# LPC2148_Engine_Room_ADUM.net
KiCad netlist of a schematic drawn in EAGLE
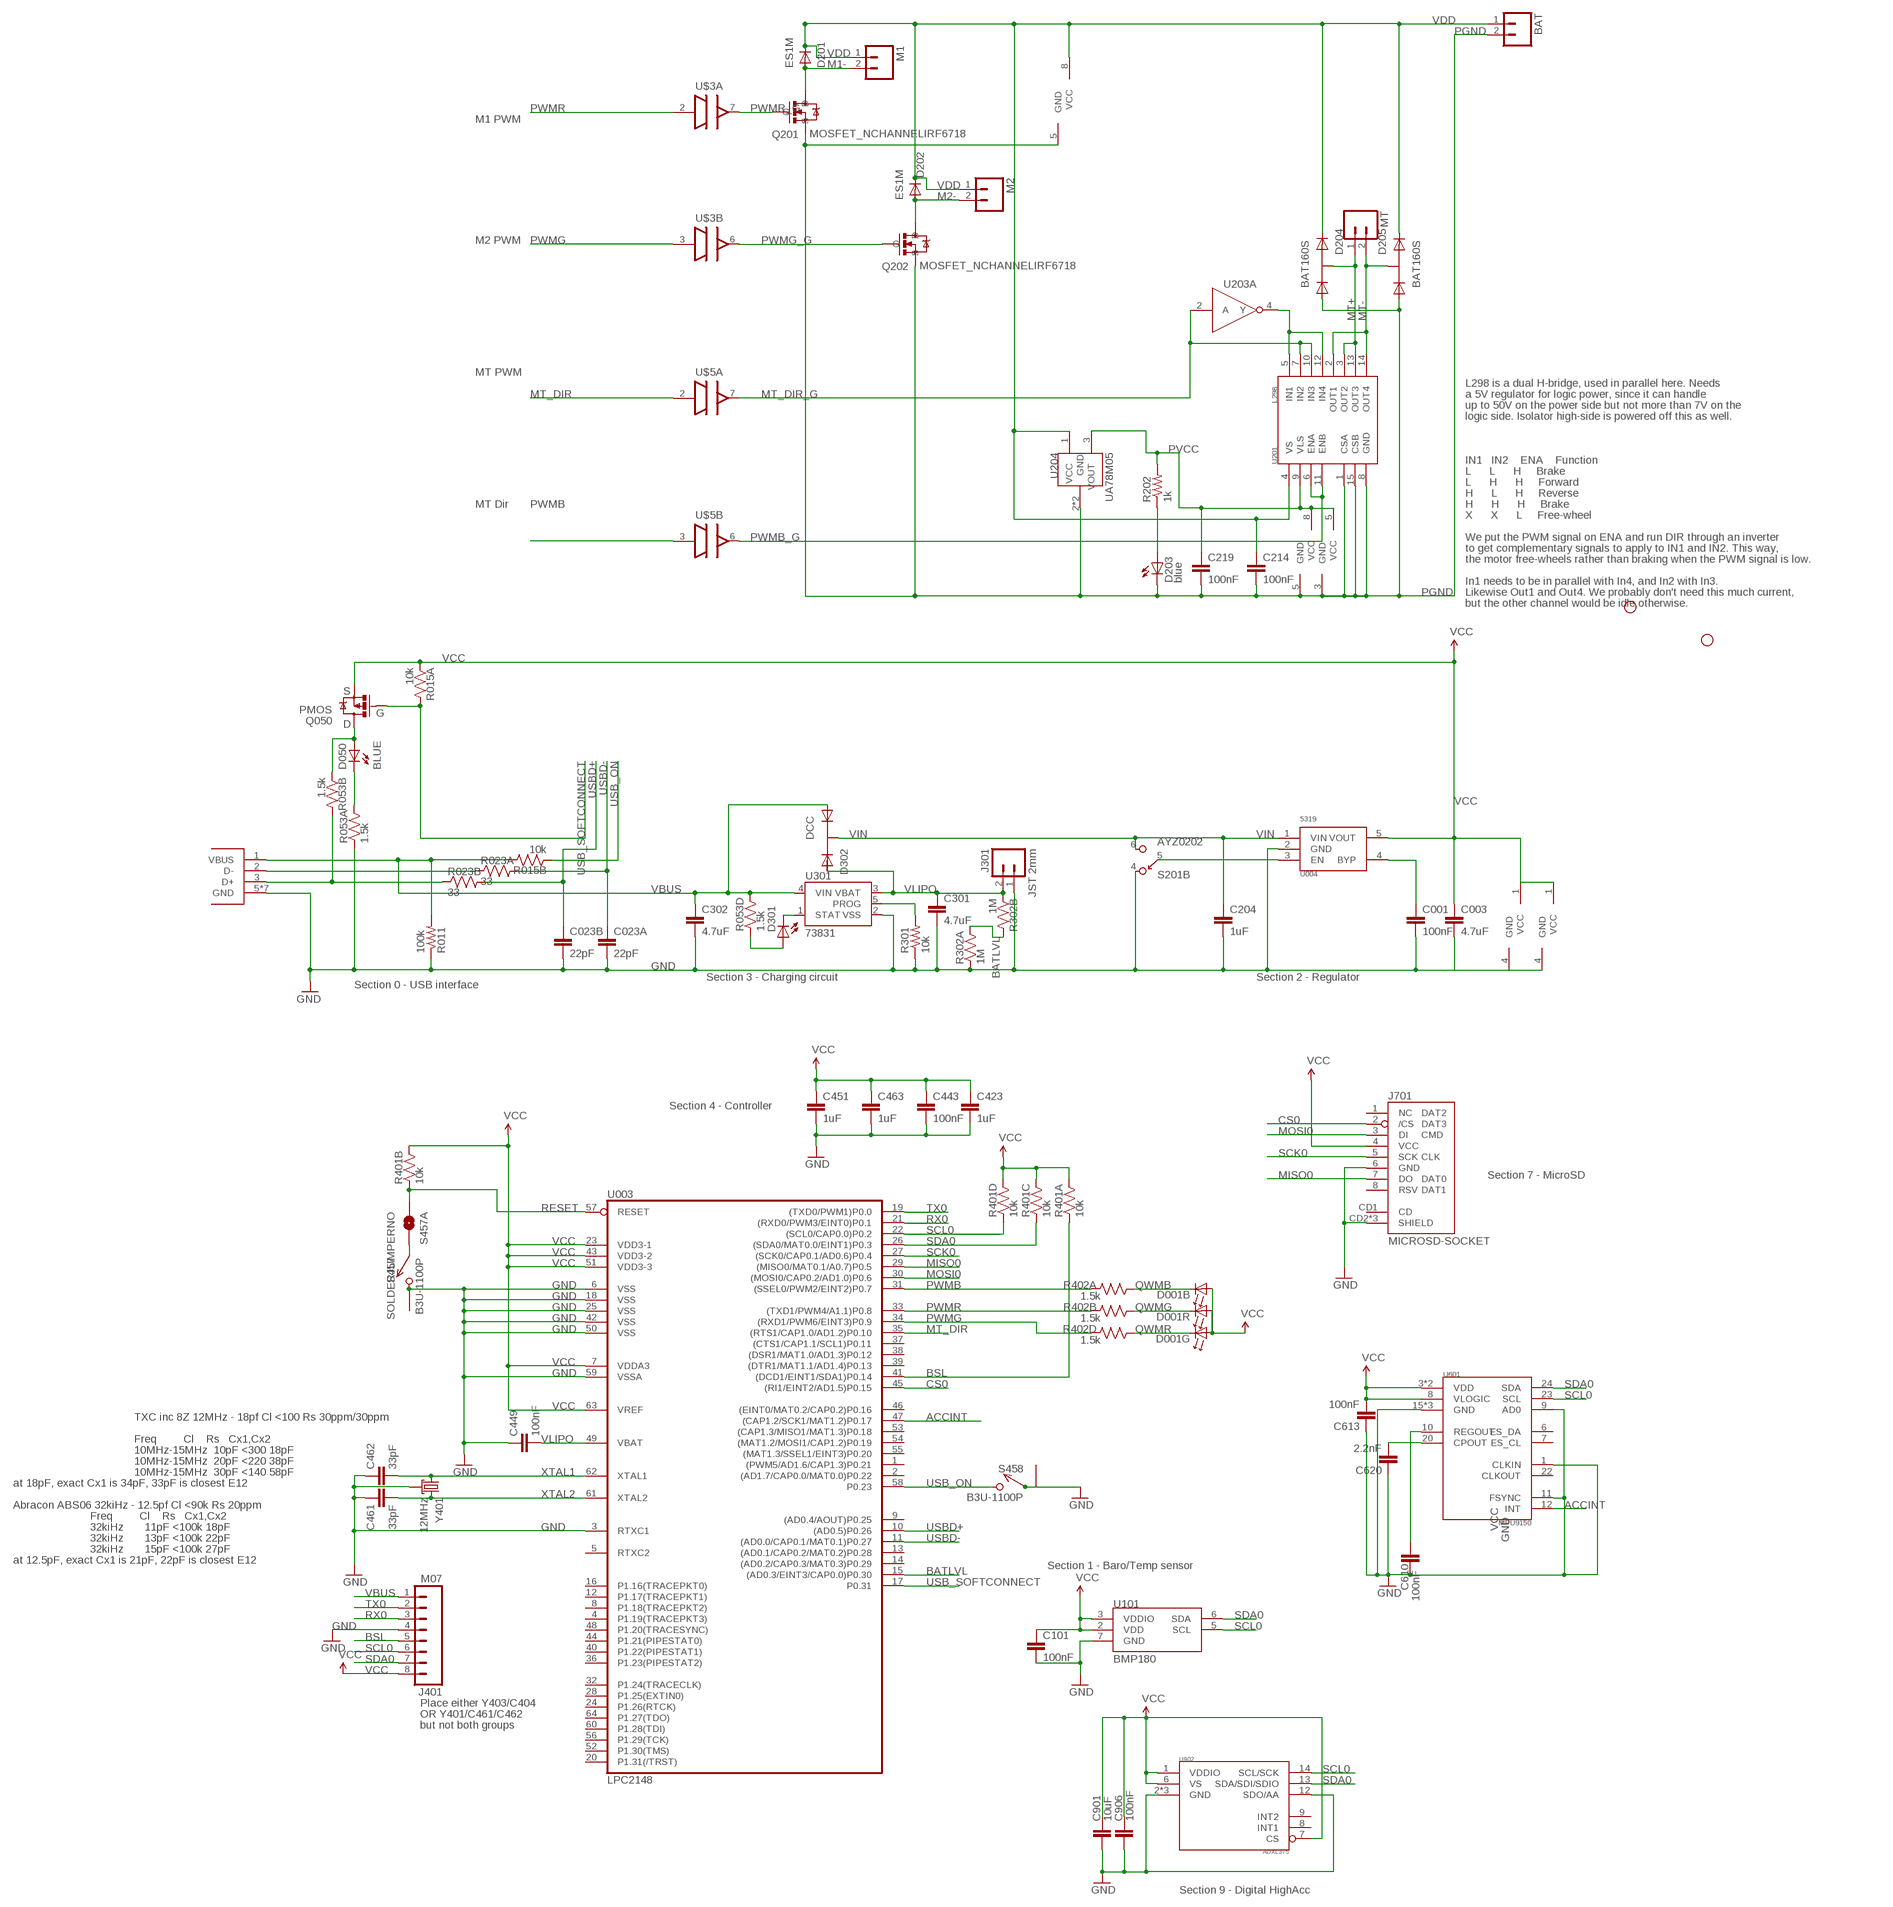
[diagram p0: schematic, sheet 1]

(export (version "E")
  (design (tool "Eeschema 10.0.6"))
  (components
    (comp (ref "BAT")
      (value "M02PTH4")
      (footprint "eagle-import:1X02_XTRA_BIG")
      (libsource (lib "eagle-import") (part "M02PTH4"))
    )
    (comp (ref "C001")
      (value "100nF")
      (footprint "eagle-import:0402-CAP")
      (libsource (lib "eagle-import") (part "CAP0402-CAP"))
    )
    (comp (ref "C003")
      (value "4.7uF")
      (footprint "eagle-import:0402-CAP")
      (libsource (lib "eagle-import") (part "CAP0402-CAP"))
    )
    (comp (ref "C023")
      (value "22pF")
      (footprint "eagle-import:CKCM25")
      (fields (field (name "DIGIKEY") "445-1860-1-ND"))
      (libsource (lib "eagle-import") (part "CKCM25"))
    )
    (comp (ref "C101")
      (value "100nF")
      (footprint "eagle-import:0402-CAP")
      (libsource (lib "eagle-import") (part "CAP0402-CAP"))
    )
    (comp (ref "C204")
      (value "1uF")
      (footprint "eagle-import:0402-CAP")
      (libsource (lib "eagle-import") (part "CAP0402-CAP"))
    )
    (comp (ref "C214")
      (value "100nF")
      (footprint "eagle-import:0402-CAP")
      (libsource (lib "eagle-import") (part "CAP0402-CAP"))
    )
    (comp (ref "C219")
      (value "100nF")
      (footprint "eagle-import:0402-CAP")
      (libsource (lib "eagle-import") (part "CAP0402-CAP"))
    )
    (comp (ref "C301")
      (value "4.7uF")
      (footprint "eagle-import:0402-CAP")
      (libsource (lib "eagle-import") (part "CAP0402-CAP"))
    )
    (comp (ref "C302")
      (value "4.7uF")
      (footprint "eagle-import:0402-CAP")
      (libsource (lib "eagle-import") (part "CAP0402-CAP"))
    )
    (comp (ref "C423")
      (value "1uF")
      (footprint "eagle-import:0402-CAP")
      (libsource (lib "eagle-import") (part "CAP0402-CAP"))
    )
    (comp (ref "C443")
      (value "100nF")
      (footprint "eagle-import:0402-CAP")
      (libsource (lib "eagle-import") (part "CAP0402-CAP"))
    )
    (comp (ref "C449")
      (value "100nF")
      (footprint "eagle-import:0402-CAP")
      (libsource (lib "eagle-import") (part "CAP0402-CAP"))
    )
    (comp (ref "C451")
      (value "1uF")
      (footprint "eagle-import:0402-CAP")
      (libsource (lib "eagle-import") (part "CAP0402-CAP"))
    )
    (comp (ref "C461")
      (value "33pF")
      (footprint "eagle-import:0402-CAP")
      (libsource (lib "eagle-import") (part "CAP0402-CAP"))
    )
    (comp (ref "C462")
      (value "33pF")
      (footprint "eagle-import:0402-CAP")
      (libsource (lib "eagle-import") (part "CAP0402-CAP"))
    )
    (comp (ref "C463")
      (value "1uF")
      (footprint "eagle-import:0402-CAP")
      (libsource (lib "eagle-import") (part "CAP0402-CAP"))
    )
    (comp (ref "C610")
      (value "100nF")
      (footprint "eagle-import:0402-CAP")
      (libsource (lib "eagle-import") (part "CAP0402-CAP"))
    )
    (comp (ref "C613")
      (value "100nF")
      (footprint "eagle-import:0402-CAP")
      (libsource (lib "eagle-import") (part "CAP0402-CAP"))
    )
    (comp (ref "C620")
      (value "2.2nF")
      (footprint "eagle-import:0402-CAP")
      (libsource (lib "eagle-import") (part "CAP0402-CAP"))
    )
    (comp (ref "C901")
      (value "10uF")
      (footprint "eagle-import:0603-CAP")
      (libsource (lib "eagle-import") (part "CAP0603-CAP"))
    )
    (comp (ref "C906")
      (value "100nF")
      (footprint "eagle-import:0402-CAP")
      (libsource (lib "eagle-import") (part "SparkFun-Passives_CAP0402-CAP"))
    )
    (comp (ref "D001")
      (value "SMLP36RGB2W(R)")
      (footprint "eagle-import:SMLP36")
      (fields (field (name "DIGIKEY") "846-1097-1-ND"))
      (libsource (lib "eagle-import") (part "SMLP36RGB2W(R)"))
    )
    (comp (ref "D050")
      (value "BLUE")
      (footprint "eagle-import:LED-0603")
      (libsource (lib "eagle-import") (part "LED0603"))
    )
    (comp (ref "D201")
      (value "ES1M")
      (footprint "eagle-import:DO-214AC")
      (libsource (lib "eagle-import") (part "DIODE-DO-214AC"))
    )
    (comp (ref "D202")
      (value "ES1M")
      (footprint "eagle-import:DO-214AC")
      (libsource (lib "eagle-import") (part "DIODE-DO-214AC"))
    )
    (comp (ref "D203")
      (value "blue")
      (footprint "eagle-import:LED-0603")
      (libsource (lib "eagle-import") (part "LED0603"))
    )
    (comp (ref "D204")
      (value "BAT160S")
      (footprint "eagle-import:SOT-223")
      (libsource (lib "eagle-import") (part "BAT160S"))
    )
    (comp (ref "D205")
      (value "BAT160S")
      (footprint "eagle-import:SOT-223")
      (libsource (lib "eagle-import") (part "BAT160S"))
    )
    (comp (ref "D301")
      (value "YELLOW")
      (footprint "eagle-import:LED-0603")
      (libsource (lib "eagle-import") (part "LED0603"))
    )
    (comp (ref "D302")
      (value "DCC")
      (footprint "eagle-import:SOT-23-3")
      (libsource (lib "eagle-import") (part "PMEG2005CT"))
    )
    (comp (ref "J004")
      (value "USB_MICROB_JSTGCT")
      (footprint "eagle-import:USB_MICROB_3075")
      (libsource (lib "eagle-import") (part "USB_MICROB_JSTGCT"))
    )
    (comp (ref "J301")
      (value "JST 2mm")
      (footprint "eagle-import:JST-2-SMD")
      (libsource (lib "eagle-import") (part "M02-JST-2MM-SMT"))
    )
    (comp (ref "J401")
      (value "M07")
      (footprint "eagle-import:1X08")
      (libsource (lib "eagle-import") (part "M081X08"))
    )
    (comp (ref "J701")
      (value "MICROSD-SOCKET")
      (footprint "eagle-import:MICROSD-SOCKET-PP")
      (libsource (lib "eagle-import") (part "MICROSD-SOCKET"))
    )
    (comp (ref "JP1")
      (value "STAND-OFF")
      (footprint "eagle-import:STAND-OFF")
      (libsource (lib "eagle-import") (part "STAND-OFF"))
    )
    (comp (ref "JP2")
      (value "STAND-OFF")
      (footprint "eagle-import:STAND-OFF")
      (libsource (lib "eagle-import") (part "STAND-OFF"))
    )
    (comp (ref "M1")
      (value "M02PTH4")
      (footprint "eagle-import:1X02_XTRA_BIG")
      (libsource (lib "eagle-import") (part "M02PTH4"))
    )
    (comp (ref "M2")
      (value "M02PTH4")
      (footprint "eagle-import:1X02_XTRA_BIG")
      (libsource (lib "eagle-import") (part "M02PTH4"))
    )
    (comp (ref "MT")
      (value "M02PTH")
      (footprint "eagle-import:1X02")
      (libsource (lib "eagle-import") (part "M02PTH"))
    )
    (comp (ref "Q050")
      (value "PMOS")
      (footprint "eagle-import:SOT23-3")
      (libsource (lib "eagle-import") (part "MOSFET-PCHANNELSMD"))
    )
    (comp (ref "Q201")
      (value "MOSFET_NCHANNELIRF6718")
      (footprint "eagle-import:DIRECTFET_L6")
      (libsource (lib "eagle-import") (part "MOSFET_NCHANNELIRF6718"))
    )
    (comp (ref "Q202")
      (value "MOSFET_NCHANNELIRF6718")
      (footprint "eagle-import:DIRECTFET_L6")
      (libsource (lib "eagle-import") (part "MOSFET_NCHANNELIRF6718"))
    )
    (comp (ref "R011")
      (value "100k")
      (footprint "eagle-import:0402-RES")
      (libsource (lib "eagle-import") (part "RESISTOR0402-RES"))
    )
    (comp (ref "R015")
      (value "10k")
      (footprint "eagle-import:CRA02")
      (fields (field (name "DIGIKEY") "Y5103CT-ND"))
      (libsource (lib "eagle-import") (part "RP2EXB24V"))
    )
    (comp (ref "R023")
      (value "33")
      (footprint "eagle-import:CRA02")
      (libsource (lib "eagle-import") (part "RP2EXB24V"))
    )
    (comp (ref "R053")
      (value "1.5k")
      (footprint "eagle-import:CRA04")
      (fields (field (name "DIGIKEY") "CRA4S81.5KCT-ND"))
      (libsource (lib "eagle-import") (part "RP404"))
    )
    (comp (ref "R202")
      (value "1k")
      (footprint "eagle-import:0402-RES")
      (libsource (lib "eagle-import") (part "RESISTOR0402-RES"))
    )
    (comp (ref "R301")
      (value "10k")
      (footprint "eagle-import:0402-RES")
      (libsource (lib "eagle-import") (part "RESISTOR0402-RES"))
    )
    (comp (ref "R302")
      (value "1M")
      (footprint "eagle-import:CRA02")
      (libsource (lib "eagle-import") (part "RP2EXB24V"))
    )
    (comp (ref "R401")
      (value "10k")
      (footprint "eagle-import:CRA04")
      (fields (field (name "DIGIKEY") "CRA4S810KCT-ND"))
      (libsource (lib "eagle-import") (part "RP404"))
    )
    (comp (ref "R402")
      (value "1.5k")
      (footprint "eagle-import:CRA04")
      (fields (field (name "DIGIKEY") "CRA4S81.5KCT-ND"))
      (libsource (lib "eagle-import") (part "RP404"))
    )
    (comp (ref "S201")
      (value "AYZ0202")
      (footprint "eagle-import:AYZ0202")
      (libsource (lib "eagle-import") (part "AYZ0202"))
    )
    (comp (ref "S457")
      (value "B3U-1100P")
      (footprint "eagle-import:B3U-1100P")
      (fields (field (name "DIGIKEY") "SW1021CT-ND"))
      (libsource (lib "eagle-import") (part "B3U-1100P"))
    )
    (comp (ref "S457A")
      (value "SOLDERJUMPERNO")
      (footprint "eagle-import:SJ_2S-NO")
      (libsource (lib "eagle-import") (part "SOLDERJUMPERNO"))
    )
    (comp (ref "S458")
      (value "B3U-1100P")
      (footprint "eagle-import:B3U-1100P")
      (fields (field (name "DIGIKEY") "SW1021CT-ND"))
      (libsource (lib "eagle-import") (part "B3U-1100P"))
    )
    (comp (ref "U$3")
      (value "ADUM3221")
      (footprint "eagle-import:SO8N")
      (libsource (lib "eagle-import") (part "ADUM3221"))
    )
    (comp (ref "U$5")
      (value "ADUM3221")
      (footprint "eagle-import:SO8N")
      (libsource (lib "eagle-import") (part "ADUM3221"))
    )
    (comp (ref "U003")
      (value "LPC2148")
      (footprint "eagle-import:SQFP-S-10X10-64")
      (libsource (lib "eagle-import") (part "LPC213X"))
    )
    (comp (ref "U004")
      (value "5319")
      (footprint "eagle-import:SOT-23-5")
      (libsource (lib "eagle-import") (part "MIC5319D5"))
    )
    (comp (ref "U101")
      (value "BMP180")
      (footprint "eagle-import:BMP180")
      (libsource (lib "eagle-import") (part "BMP180"))
    )
    (comp (ref "U201")
      (value "L298")
      (footprint "eagle-import:MULTIWATT15")
      (libsource (lib "eagle-import") (part "L298"))
    )
    (comp (ref "U203")
      (value "MC74VHC1G04")
      (footprint "eagle-import:SOT-23-5")
      (libsource (lib "eagle-import") (part "MC74VHC1G04"))
    )
    (comp (ref "U204")
      (value "UA78M05")
      (footprint "eagle-import:SOT-223")
      (libsource (lib "eagle-import") (part "UA78M05"))
    )
    (comp (ref "U301")
      (value "73831")
      (footprint "eagle-import:SOT23-5")
      (libsource (lib "eagle-import") (part "MCP73831"))
    )
    (comp (ref "U601")
      (value "MPU9150")
      (footprint "eagle-import:LLGA24")
      (libsource (lib "eagle-import") (part "MPU9150"))
    )
    (comp (ref "U902")
      (value "ADXL375")
      (footprint "eagle-import:ADXL375")
      (libsource (lib "eagle-import") (part "ADXL375"))
    )
    (comp (ref "Y401")
      (value "12MHz")
      (footprint "eagle-import:CRYSTAL_SMD_2MM_2_5MM")
      (libsource (lib "eagle-import") (part "CX2520"))
    )
  )
  (nets
    (net (code "1") (name "/ACCINT") (class "Default")
      (node (ref "U003") (pin "47") (pinfunction "(CAP1.2/SCK1/MAT1.2)P0.17_47") (pintype "bidirectional"))
      (node (ref "U601") (pin "12") (pinfunction "INT_12") (pintype "bidirectional"))
    )
    (net (code "2") (name "/BATLVL") (class "Default")
      (node (ref "R302") (pin "3") (pinfunction "2_3") (pintype "passive"))
      (node (ref "R302") (pin "4") (pinfunction "2_4") (pintype "passive"))
      (node (ref "U003") (pin "15") (pinfunction "(AD0.3/EINT3/CAP0.0)P0.30_15") (pintype "bidirectional"))
    )
    (net (code "3") (name "/BSL") (class "Default")
      (node (ref "J401") (pin "5") (pinfunction "5_5") (pintype "passive"))
      (node (ref "R401") (pin "1") (pinfunction "1_1") (pintype "passive"))
      (node (ref "U003") (pin "41") (pinfunction "(DCD1/EINT1/SDA1)P0.14_41") (pintype "bidirectional"))
    )
    (net (code "4") (name "/CS0") (class "Default")
      (node (ref "J701") (pin "2") (pinfunction "/CS_2") (pintype "bidirectional"))
      (node (ref "U003") (pin "45") (pinfunction "(RI1/EINT2/AD1.5)P0.15_45") (pintype "bidirectional"))
    )
    (net (code "5") (name "/M1-") (class "Default")
      (node (ref "D201") (pin "A") (pinfunction "A_A") (pintype "passive"))
      (node (ref "M1") (pin "2") (pinfunction "2_2") (pintype "passive"))
      (node (ref "Q201") (pin "D1") (pinfunction "D_D1") (pintype "passive"))
      (node (ref "Q201") (pin "D2") (pinfunction "D_D2") (pintype "passive"))
    )
    (net (code "6") (name "/M2-") (class "Default")
      (node (ref "D202") (pin "A") (pinfunction "A_A") (pintype "passive"))
      (node (ref "M2") (pin "2") (pinfunction "2_2") (pintype "passive"))
      (node (ref "Q202") (pin "D1") (pinfunction "D_D1") (pintype "passive"))
      (node (ref "Q202") (pin "D2") (pinfunction "D_D2") (pintype "passive"))
    )
    (net (code "7") (name "/MISO0") (class "Default")
      (node (ref "J701") (pin "7") (pinfunction "DO_7") (pintype "bidirectional"))
      (node (ref "U003") (pin "29") (pinfunction "(MISO0/MAT0.1/A0.7)P0.5_29") (pintype "bidirectional"))
    )
    (net (code "8") (name "/MOSI0") (class "Default")
      (node (ref "J701") (pin "3") (pinfunction "DI_3") (pintype "bidirectional"))
      (node (ref "U003") (pin "30") (pinfunction "(MOSI0/CAP0.2/AD1.0)P0.6_30") (pintype "bidirectional"))
    )
    (net (code "9") (name "/MT+") (class "Default")
      (node (ref "D204") (pin "4") (pinfunction "K1A2_4") (pintype "passive"))
      (node (ref "MT") (pin "1") (pinfunction "1_1") (pintype "passive"))
      (node (ref "U201") (pin "13") (pinfunction "OUT3_13") (pintype "bidirectional"))
      (node (ref "U201") (pin "3") (pinfunction "OUT2_3") (pintype "bidirectional"))
    )
    (net (code "10") (name "/MT-") (class "Default")
      (node (ref "D205") (pin "4") (pinfunction "K1A2_4") (pintype "passive"))
      (node (ref "MT") (pin "2") (pinfunction "2_2") (pintype "passive"))
      (node (ref "U201") (pin "14") (pinfunction "OUT4_14") (pintype "bidirectional"))
      (node (ref "U201") (pin "2") (pinfunction "OUT1_2") (pintype "bidirectional"))
    )
    (net (code "11") (name "/MT_DIR") (class "Default")
      (node (ref "U$5") (pin "2") (pinfunction "IN_2") (pintype "input"))
      (node (ref "U003") (pin "35") (pinfunction "(RTS1/CAP1.0/AD1.2)P0.10_35") (pintype "bidirectional"))
    )
    (net (code "12") (name "/MT_DIR_G") (class "Default")
      (node (ref "U$5") (pin "7") (pinfunction "OUT_7") (pintype "bidirectional"))
      (node (ref "U201") (pin "10") (pinfunction "IN3_10") (pintype "bidirectional"))
      (node (ref "U201") (pin "7") (pinfunction "IN2_7") (pintype "bidirectional"))
      (node (ref "U203") (pin "2") (pinfunction "A_2") (pintype "input"))
    )
    (net (code "13") (name "/PGND") (class "Default")
      (node (ref "BAT") (pin "2") (pinfunction "2_2") (pintype "passive"))
      (node (ref "C214") (pin "2") (pinfunction "2_2") (pintype "passive"))
      (node (ref "C219") (pin "2") (pinfunction "2_2") (pintype "passive"))
      (node (ref "D203") (pin "C") (pinfunction "C_C") (pintype "passive"))
      (node (ref "D204") (pin "1") (pinfunction "A1_1") (pintype "passive"))
      (node (ref "D205") (pin "1") (pinfunction "A1_1") (pintype "passive"))
      (node (ref "Q201") (pin "S") (pinfunction "S_S") (pintype "passive"))
      (node (ref "Q202") (pin "S") (pinfunction "S_S") (pintype "passive"))
      (node (ref "U$3") (pin "5") (pinfunction "GND_5") (pintype "bidirectional"))
      (node (ref "U$5") (pin "5") (pinfunction "GND_5") (pintype "bidirectional"))
      (node (ref "U201") (pin "1") (pinfunction "CSA_1") (pintype "bidirectional"))
      (node (ref "U201") (pin "15") (pinfunction "CSB_15") (pintype "bidirectional"))
      (node (ref "U201") (pin "8") (pinfunction "GND_8") (pintype "bidirectional"))
      (node (ref "U203") (pin "3") (pinfunction "GND_3") (pintype "bidirectional"))
      (node (ref "U204") (pin "2") (pinfunction "GND_2") (pintype "bidirectional"))
      (node (ref "U204") (pin "4") (pinfunction "GND_4") (pintype "bidirectional"))
    )
    (net (code "14") (name "/PVCC") (class "Default")
      (node (ref "C219") (pin "1") (pinfunction "1_1") (pintype "passive"))
      (node (ref "R202") (pin "2") (pinfunction "2_2") (pintype "passive"))
      (node (ref "U$5") (pin "8") (pinfunction "VCC_8") (pintype "bidirectional"))
      (node (ref "U201") (pin "9") (pinfunction "VLS_9") (pintype "bidirectional"))
      (node (ref "U203") (pin "5") (pinfunction "VCC_5") (pintype "bidirectional"))
      (node (ref "U204") (pin "3") (pinfunction "VOUT_3") (pintype "bidirectional"))
    )
    (net (code "15") (name "/PWMB") (class "Default")
      (node (ref "R402") (pin "8") (pinfunction "2_8") (pintype "passive"))
      (node (ref "U$5") (pin "3") (pinfunction "IN_3") (pintype "input"))
      (node (ref "U003") (pin "31") (pinfunction "(SSEL0/PWM2/EINT2)P0.7_31") (pintype "bidirectional"))
    )
    (net (code "16") (name "/PWMB_G") (class "Default")
      (node (ref "U$5") (pin "6") (pinfunction "OUT_6") (pintype "bidirectional"))
      (node (ref "U201") (pin "11") (pinfunction "ENB_11") (pintype "bidirectional"))
      (node (ref "U201") (pin "6") (pinfunction "ENA_6") (pintype "bidirectional"))
    )
    (net (code "17") (name "/PWMG") (class "Default")
      (node (ref "R402") (pin "5") (pinfunction "2_5") (pintype "passive"))
      (node (ref "U$3") (pin "3") (pinfunction "IN_3") (pintype "input"))
      (node (ref "U003") (pin "34") (pinfunction "(RXD1/PWM6/EINT3)P0.9_34") (pintype "bidirectional"))
    )
    (net (code "18") (name "/PWMG_G") (class "Default")
      (node (ref "Q202") (pin "G") (pinfunction "G_G") (pintype "passive"))
      (node (ref "U$3") (pin "6") (pinfunction "OUT_6") (pintype "bidirectional"))
    )
    (net (code "19") (name "/PWMR") (class "Default")
      (node (ref "R402") (pin "7") (pinfunction "2_7") (pintype "passive"))
      (node (ref "U$3") (pin "2") (pinfunction "IN_2") (pintype "input"))
      (node (ref "U003") (pin "33") (pinfunction "(TXD1/PWM4/A1.1)P0.8_33") (pintype "bidirectional"))
    )
    (net (code "20") (name "/PWMR_G") (class "Default")
      (node (ref "Q201") (pin "G") (pinfunction "G_G") (pintype "passive"))
      (node (ref "U$3") (pin "7") (pinfunction "OUT_7") (pintype "bidirectional"))
    )
    (net (code "21") (name "/QWMB") (class "Default")
      (node (ref "D001") (pin "1") (pinfunction "C_1") (pintype "passive"))
      (node (ref "R402") (pin "1") (pinfunction "1_1") (pintype "passive"))
    )
    (net (code "22") (name "/QWMG") (class "Default")
      (node (ref "D001") (pin "5") (pinfunction "C_5") (pintype "passive"))
      (node (ref "R402") (pin "4") (pinfunction "1_4") (pintype "passive"))
    )
    (net (code "23") (name "/QWMR") (class "Default")
      (node (ref "D001") (pin "3") (pinfunction "C_3") (pintype "passive"))
      (node (ref "R402") (pin "2") (pinfunction "1_2") (pintype "passive"))
    )
    (net (code "24") (name "/RESET") (class "Default")
      (node (ref "R401") (pin "2") (pinfunction "1_2") (pintype "passive"))
      (node (ref "S457A") (pin "1") (pinfunction "1_1") (pintype "passive"))
      (node (ref "U003") (pin "57") (pinfunction "RESET_57") (pintype "input"))
    )
    (net (code "25") (name "/RX0") (class "Default")
      (node (ref "J401") (pin "3") (pinfunction "3_3") (pintype "passive"))
      (node (ref "U003") (pin "21") (pinfunction "(RXD0/PWM3/EINT0)P0.1_21") (pintype "bidirectional"))
    )
    (net (code "26") (name "/SCK0") (class "Default")
      (node (ref "J701") (pin "5") (pinfunction "SCK_5") (pintype "bidirectional"))
      (node (ref "U003") (pin "27") (pinfunction "(SCK0/CAP0.1/AD0.6)P0.4_27") (pintype "bidirectional"))
    )
    (net (code "27") (name "/SCL0") (class "Default")
      (node (ref "J401") (pin "6") (pinfunction "6_6") (pintype "passive"))
      (node (ref "R401") (pin "4") (pinfunction "1_4") (pintype "passive"))
      (node (ref "U003") (pin "22") (pinfunction "(SCL0/CAP0.0)P0.2_22") (pintype "bidirectional"))
      (node (ref "U101") (pin "5") (pinfunction "SCL_5") (pintype "input"))
      (node (ref "U601") (pin "23") (pinfunction "SCL_23") (pintype "bidirectional"))
      (node (ref "U902") (pin "14") (pinfunction "SCL/SCK_14") (pintype "input"))
    )
    (net (code "28") (name "/SDA0") (class "Default")
      (node (ref "J401") (pin "7") (pinfunction "7_7") (pintype "passive"))
      (node (ref "R401") (pin "3") (pinfunction "1_3") (pintype "passive"))
      (node (ref "U003") (pin "26") (pinfunction "(SDA0/MAT0.0/EINT1)P0.3_26") (pintype "bidirectional"))
      (node (ref "U101") (pin "6") (pinfunction "SDA_6") (pintype "bidirectional"))
      (node (ref "U601") (pin "24") (pinfunction "SDA_24") (pintype "bidirectional"))
      (node (ref "U902") (pin "13") (pinfunction "SDA/SDI/SDIO_13") (pintype "bidirectional"))
    )
    (net (code "29") (name "/TX0") (class "Default")
      (node (ref "J401") (pin "2") (pinfunction "2_2") (pintype "passive"))
      (node (ref "U003") (pin "19") (pinfunction "(TXD0/PWM1)P0.0_19") (pintype "bidirectional"))
    )
    (net (code "30") (name "/USBD+") (class "Default")
      (node (ref "C023") (pin "2") (pinfunction "1_2") (pintype "passive"))
      (node (ref "R023") (pin "3") (pinfunction "2_3") (pintype "passive"))
      (node (ref "U003") (pin "10") (pinfunction "(AD0.5)P0.26_10") (pintype "bidirectional"))
    )
    (net (code "31") (name "/USBD-") (class "Default")
      (node (ref "C023") (pin "1") (pinfunction "1_1") (pintype "passive"))
      (node (ref "R023") (pin "4") (pinfunction "2_4") (pintype "passive"))
      (node (ref "U003") (pin "11") (pinfunction "(AD0.0/CAP0.1/MAT0.1)P0.27_11") (pintype "bidirectional"))
    )
    (net (code "32") (name "/USB_ON") (class "Default")
      (node (ref "R015") (pin "2") (pinfunction "1_2") (pintype "passive"))
      (node (ref "S458") (pin "P$2") (pinfunction "2_P$2") (pintype "bidirectional"))
      (node (ref "U003") (pin "58") (pinfunction "P0.23_58") (pintype "bidirectional"))
    )
    (net (code "33") (name "/USB_SOFTCONNECT") (class "Default")
      (node (ref "Q050") (pin "1") (pinfunction "G_1") (pintype "passive"))
      (node (ref "R015") (pin "4") (pinfunction "2_4") (pintype "passive"))
      (node (ref "U003") (pin "17") (pinfunction "P0.31_17") (pintype "output"))
    )
    (net (code "34") (name "/VBUS") (class "Default")
      (node (ref "C302") (pin "1") (pinfunction "1_1") (pintype "passive"))
      (node (ref "D302") (pin "1") (pinfunction "A1_1") (pintype "passive"))
      (node (ref "J004") (pin "1") (pinfunction "VBUS_1") (pintype "bidirectional"))
      (node (ref "J401") (pin "1") (pinfunction "1_1") (pintype "passive"))
      (node (ref "R011") (pin "2") (pinfunction "2_2") (pintype "passive"))
      (node (ref "R015") (pin "3") (pinfunction "2_3") (pintype "passive"))
      (node (ref "R053") (pin "5") (pinfunction "2_5") (pintype "passive"))
      (node (ref "U301") (pin "4") (pinfunction "VIN_4") (pintype "power_in"))
    )
    (net (code "35") (name "/VDD") (class "Default")
      (node (ref "BAT") (pin "1") (pinfunction "1_1") (pintype "passive"))
      (node (ref "C214") (pin "1") (pinfunction "1_1") (pintype "passive"))
      (node (ref "D201") (pin "C") (pinfunction "C_C") (pintype "passive"))
      (node (ref "D202") (pin "C") (pinfunction "C_C") (pintype "passive"))
      (node (ref "D204") (pin "3") (pinfunction "K2_3") (pintype "passive"))
      (node (ref "D205") (pin "3") (pinfunction "K2_3") (pintype "passive"))
      (node (ref "M1") (pin "1") (pinfunction "1_1") (pintype "passive"))
      (node (ref "M2") (pin "1") (pinfunction "1_1") (pintype "passive"))
      (node (ref "U$3") (pin "8") (pinfunction "VCC_8") (pintype "bidirectional"))
      (node (ref "U201") (pin "4") (pinfunction "VS_4") (pintype "bidirectional"))
      (node (ref "U204") (pin "1") (pinfunction "VCC_1") (pintype "bidirectional"))
    )
    (net (code "36") (name "/VIN") (class "Default")
      (node (ref "C204") (pin "1") (pinfunction "1_1") (pintype "passive"))
      (node (ref "D302") (pin "3") (pinfunction "K_3") (pintype "passive"))
      (node (ref "S201") (pin "6") (pinfunction "P$2_6") (pintype "bidirectional"))
      (node (ref "U004") (pin "1") (pinfunction "VIN_1") (pintype "bidirectional"))
    )
    (net (code "37") (name "/VLIPO") (class "Default")
      (node (ref "C301") (pin "1") (pinfunction "1_1") (pintype "passive"))
      (node (ref "C449") (pin "2") (pinfunction "2_2") (pintype "passive"))
      (node (ref "D302") (pin "2") (pinfunction "A2_2") (pintype "passive"))
      (node (ref "J301") (pin "2") (pinfunction "2_2") (pintype "passive"))
      (node (ref "R302") (pin "2") (pinfunction "1_2") (pintype "passive"))
      (node (ref "U003") (pin "49") (pinfunction "VBAT_49") (pintype "power_in"))
      (node (ref "U301") (pin "3") (pinfunction "VBAT_3") (pintype "power_in"))
    )
    (net (code "38") (name "/XTAL1") (class "Default")
      (node (ref "C462") (pin "2") (pinfunction "2_2") (pintype "passive"))
      (node (ref "U003") (pin "62") (pinfunction "XTAL1_62") (pintype "input"))
      (node (ref "Y401") (pin "1") (pinfunction "1_1") (pintype "passive"))
    )
    (net (code "39") (name "/XTAL2") (class "Default")
      (node (ref "C461") (pin "2") (pinfunction "2_2") (pintype "passive"))
      (node (ref "U003") (pin "61") (pinfunction "XTAL2_61") (pintype "output"))
      (node (ref "Y401") (pin "3") (pinfunction "2_3") (pintype "passive"))
    )
    (net (code "40") (name "GND") (class "Default")
      (node (ref "C001") (pin "2") (pinfunction "2_2") (pintype "passive"))
      (node (ref "C003") (pin "2") (pinfunction "2_2") (pintype "passive"))
      (node (ref "C023") (pin "3") (pinfunction "2_3") (pintype "passive"))
      (node (ref "C023") (pin "4") (pinfunction "2_4") (pintype "passive"))
      (node (ref "C101") (pin "2") (pinfunction "2_2") (pintype "passive"))
      (node (ref "C204") (pin "2") (pinfunction "2_2") (pintype "passive"))
      (node (ref "C301") (pin "2") (pinfunction "2_2") (pintype "passive"))
      (node (ref "C302") (pin "2") (pinfunction "2_2") (pintype "passive"))
      (node (ref "C423") (pin "2") (pinfunction "2_2") (pintype "passive"))
      (node (ref "C443") (pin "2") (pinfunction "2_2") (pintype "passive"))
      (node (ref "C449") (pin "1") (pinfunction "1_1") (pintype "passive"))
      (node (ref "C451") (pin "2") (pinfunction "2_2") (pintype "passive"))
      (node (ref "C461") (pin "1") (pinfunction "1_1") (pintype "passive"))
      (node (ref "C462") (pin "1") (pinfunction "1_1") (pintype "passive"))
      (node (ref "C463") (pin "2") (pinfunction "2_2") (pintype "passive"))
      (node (ref "C610") (pin "2") (pinfunction "2_2") (pintype "passive"))
      (node (ref "C613") (pin "1") (pinfunction "1_1") (pintype "passive"))
      (node (ref "C620") (pin "1") (pinfunction "1_1") (pintype "passive"))
      (node (ref "C901") (pin "2") (pinfunction "2_2") (pintype "passive"))
      (node (ref "C906") (pin "2") (pinfunction "2_2") (pintype "passive"))
      (node (ref "J004") (pin "5") (pinfunction "GND_5") (pintype "bidirectional"))
      (node (ref "J004") (pin "P$1") (pinfunction "GND_P$1") (pintype "bidirectional"))
      (node (ref "J004") (pin "P$10") (pinfunction "GND_P$10") (pintype "bidirectional"))
      (node (ref "J004") (pin "P$2") (pinfunction "GND_P$2") (pintype "bidirectional"))
      (node (ref "J004") (pin "P$3") (pinfunction "GND_P$3") (pintype "bidirectional"))
      (node (ref "J004") (pin "P$4") (pinfunction "GND_P$4") (pintype "bidirectional"))
      (node (ref "J004") (pin "P$8") (pinfunction "GND_P$8") (pintype "bidirectional"))
      (node (ref "J301") (pin "1") (pinfunction "1_1") (pintype "passive"))
      (node (ref "J401") (pin "4") (pinfunction "4_4") (pintype "passive"))
      (node (ref "J701") (pin "6") (pinfunction "GND_6") (pintype "bidirectional"))
      (node (ref "J701") (pin "CD2") (pinfunction "SHIELD_CD2") (pintype "bidirectional"))
      (node (ref "J701") (pin "GND1") (pinfunction "SHIELD_GND1") (pintype "bidirectional"))
      (node (ref "J701") (pin "GND3") (pinfunction "SHIELD_GND3") (pintype "bidirectional"))
      (node (ref "R011") (pin "1") (pinfunction "1_1") (pintype "passive"))
      (node (ref "R053") (pin "1") (pinfunction "1_1") (pintype "passive"))
      (node (ref "R301") (pin "1") (pinfunction "1_1") (pintype "passive"))
      (node (ref "R302") (pin "1") (pinfunction "1_1") (pintype "passive"))
      (node (ref "S201") (pin "4") (pinfunction "P$1_4") (pintype "bidirectional"))
      (node (ref "S457") (pin "P$2") (pinfunction "2_P$2") (pintype "bidirectional"))
      (node (ref "S457") (pin "P$3") (pinfunction "1_P$3") (pintype "bidirectional"))
      (node (ref "S458") (pin "P$1") (pinfunction "1_P$1") (pintype "bidirectional"))
      (node (ref "S458") (pin "P$3") (pinfunction "1_P$3") (pintype "bidirectional"))
      (node (ref "U$3") (pin "4") (pinfunction "GND_4") (pintype "bidirectional"))
      (node (ref "U$5") (pin "4") (pinfunction "GND_4") (pintype "bidirectional"))
      (node (ref "U003") (pin "18") (pinfunction "VSS_18") (pintype "power_in"))
      (node (ref "U003") (pin "25") (pinfunction "VSS_25") (pintype "power_in"))
      (node (ref "U003") (pin "3") (pinfunction "RTXC1_3") (pintype "input"))
      (node (ref "U003") (pin "42") (pinfunction "VSS_42") (pintype "power_in"))
      (node (ref "U003") (pin "50") (pinfunction "VSS_50") (pintype "power_in"))
      (node (ref "U003") (pin "59") (pinfunction "VSSA_59") (pintype "power_in"))
      (node (ref "U003") (pin "6") (pinfunction "VSS_6") (pintype "power_in"))
      (node (ref "U004") (pin "2") (pinfunction "GND_2") (pintype "bidirectional"))
      (node (ref "U101") (pin "7") (pinfunction "GND_7") (pintype "power_in"))
      (node (ref "U301") (pin "2") (pinfunction "VSS_2") (pintype "power_in"))
      (node (ref "U601") (pin "1") (pinfunction "CLKIN_1") (pintype "bidirectional"))
      (node (ref "U601") (pin "11") (pinfunction "FSYNC_11") (pintype "bidirectional"))
      (node (ref "U601") (pin "15") (pinfunction "GND_15") (pintype "bidirectional"))
      (node (ref "U601") (pin "17") (pinfunction "GND_17") (pintype "bidirectional"))
      (node (ref "U601") (pin "18") (pinfunction "GND_18") (pintype "bidirectional"))
      (node (ref "U601") (pin "9") (pinfunction "AD0_9") (pintype "bidirectional"))
      (node (ref "U902") (pin "12") (pinfunction "SDO/AA_12") (pintype "bidirectional"))
      (node (ref "U902") (pin "2") (pinfunction "GND_2") (pintype "power_in"))
      (node (ref "U902") (pin "4") (pinfunction "GND_4") (pintype "power_in"))
      (node (ref "U902") (pin "5") (pinfunction "GND_5") (pintype "power_in"))
      (node (ref "Y401") (pin "2") (pinfunction "GND_2") (pintype "passive"))
      (node (ref "Y401") (pin "4") (pinfunction "GND_4") (pintype "passive"))
    )
    (net (code "41") (name "Net-(D203-PadA)") (class "Default")
      (node (ref "D203") (pin "A") (pinfunction "A_A") (pintype "passive"))
      (node (ref "R202") (pin "1") (pinfunction "1_1") (pintype "passive"))
    )
    (net (code "42") (name "Net-(J004-D+)") (class "Default")
      (node (ref "J004") (pin "3") (pinfunction "D+_3") (pintype "bidirectional"))
      (node (ref "R023") (pin "2") (pinfunction "1_2") (pintype "passive"))
      (node (ref "R053") (pin "7") (pinfunction "2_7") (pintype "passive"))
    )
    (net (code "43") (name "Net-(J004-D-)") (class "Default")
      (node (ref "J004") (pin "2") (pinfunction "D-_2") (pintype "bidirectional"))
      (node (ref "R023") (pin "1") (pinfunction "1_1") (pintype "passive"))
    )
    (net (code "44") (name "Net-(Q050-D)") (class "Default")
      (node (ref "D050") (pin "A") (pinfunction "A_A") (pintype "passive"))
      (node (ref "Q050") (pin "3") (pinfunction "D_3") (pintype "passive"))
      (node (ref "R053") (pin "2") (pinfunction "1_2") (pintype "passive"))
    )
    (net (code "45") (name "Net-(R053A-2)") (class "Default")
      (node (ref "D050") (pin "C") (pinfunction "C_C") (pintype "passive"))
      (node (ref "R053") (pin "8") (pinfunction "2_8") (pintype "passive"))
    )
    (net (code "46") (name "Net-(R053D-1)") (class "Default")
      (node (ref "D301") (pin "A") (pinfunction "A_A") (pintype "passive"))
      (node (ref "R053") (pin "4") (pinfunction "1_4") (pintype "passive"))
    )
    (net (code "47") (name "Net-(S201B-P$3)") (class "Default")
      (node (ref "S201") (pin "5") (pinfunction "P$3_5") (pintype "bidirectional"))
      (node (ref "U004") (pin "3") (pinfunction "EN_3") (pintype "bidirectional"))
    )
    (net (code "48") (name "Net-(S457B-1)") (class "Default")
      (node (ref "S457") (pin "P$1") (pinfunction "1_P$1") (pintype "bidirectional"))
      (node (ref "S457A") (pin "2") (pinfunction "2_2") (pintype "passive"))
    )
    (net (code "49") (name "Net-(U004-BYP)") (class "Default")
      (node (ref "C001") (pin "1") (pinfunction "1_1") (pintype "passive"))
      (node (ref "U004") (pin "4") (pinfunction "BYP_4") (pintype "bidirectional"))
    )
    (net (code "50") (name "Net-(U201-IN1)") (class "Default")
      (node (ref "U201") (pin "12") (pinfunction "IN4_12") (pintype "bidirectional"))
      (node (ref "U201") (pin "5") (pinfunction "IN1_5") (pintype "bidirectional"))
      (node (ref "U203") (pin "4") (pinfunction "Y_4") (pintype "output"))
    )
    (net (code "51") (name "Net-(U301-PROG)") (class "Default")
      (node (ref "R301") (pin "2") (pinfunction "2_2") (pintype "passive"))
      (node (ref "U301") (pin "5") (pinfunction "PROG_5") (pintype "input"))
    )
    (net (code "52") (name "Net-(U301-STAT)") (class "Default")
      (node (ref "D301") (pin "C") (pinfunction "C_C") (pintype "passive"))
      (node (ref "U301") (pin "1") (pinfunction "STAT_1") (pintype "output"))
    )
    (net (code "53") (name "Net-(U601-CPOUT)") (class "Default")
      (node (ref "C620") (pin "2") (pinfunction "2_2") (pintype "passive"))
      (node (ref "U601") (pin "20") (pinfunction "CPOUT_20") (pintype "bidirectional"))
    )
    (net (code "54") (name "Net-(U601-REGOUT)") (class "Default")
      (node (ref "C610") (pin "1") (pinfunction "1_1") (pintype "passive"))
      (node (ref "U601") (pin "10") (pinfunction "REGOUT_10") (pintype "bidirectional"))
    )
    (net (code "55") (name "VCC") (class "Default")
      (node (ref "C003") (pin "1") (pinfunction "1_1") (pintype "passive"))
      (node (ref "C101") (pin "1") (pinfunction "1_1") (pintype "passive"))
      (node (ref "C423") (pin "1") (pinfunction "1_1") (pintype "passive"))
      (node (ref "C443") (pin "1") (pinfunction "1_1") (pintype "passive"))
      (node (ref "C451") (pin "1") (pinfunction "1_1") (pintype "passive"))
      (node (ref "C463") (pin "1") (pinfunction "1_1") (pintype "passive"))
      (node (ref "C613") (pin "2") (pinfunction "2_2") (pintype "passive"))
      (node (ref "C901") (pin "1") (pinfunction "1_1") (pintype "passive"))
      (node (ref "C906") (pin "1") (pinfunction "1_1") (pintype "passive"))
      (node (ref "D001") (pin "2") (pinfunction "A_2") (pintype "passive"))
      (node (ref "D001") (pin "4") (pinfunction "A_4") (pintype "passive"))
      (node (ref "D001") (pin "6") (pinfunction "A_6") (pintype "passive"))
      (node (ref "J401") (pin "8") (pinfunction "8_8") (pintype "passive"))
      (node (ref "J701") (pin "4") (pinfunction "VCC_4") (pintype "bidirectional"))
      (node (ref "Q050") (pin "2") (pinfunction "S_2") (pintype "passive"))
      (node (ref "R015") (pin "1") (pinfunction "1_1") (pintype "passive"))
      (node (ref "R401") (pin "5") (pinfunction "2_5") (pintype "passive"))
      (node (ref "R401") (pin "6") (pinfunction "2_6") (pintype "passive"))
      (node (ref "R401") (pin "7") (pinfunction "2_7") (pintype "passive"))
      (node (ref "R401") (pin "8") (pinfunction "2_8") (pintype "passive"))
      (node (ref "U$3") (pin "1") (pinfunction "VCC_1") (pintype "bidirectional"))
      (node (ref "U$5") (pin "1") (pinfunction "VCC_1") (pintype "bidirectional"))
      (node (ref "U003") (pin "23") (pinfunction "VDD3-1_23") (pintype "power_in"))
      (node (ref "U003") (pin "43") (pinfunction "VDD3-2_43") (pintype "power_in"))
      (node (ref "U003") (pin "51") (pinfunction "VDD3-3_51") (pintype "power_in"))
      (node (ref "U003") (pin "63") (pinfunction "VREF_63") (pintype "input"))
      (node (ref "U003") (pin "7") (pinfunction "VDDA3_7") (pintype "power_in"))
      (node (ref "U004") (pin "5") (pinfunction "VOUT_5") (pintype "bidirectional"))
      (node (ref "U101") (pin "2") (pinfunction "VDD_2") (pintype "power_in"))
      (node (ref "U101") (pin "3") (pinfunction "VDDIO_3") (pintype "power_in"))
      (node (ref "U601") (pin "13") (pinfunction "VDD_13") (pintype "bidirectional"))
      (node (ref "U601") (pin "3") (pinfunction "VDD_3") (pintype "bidirectional"))
      (node (ref "U601") (pin "8") (pinfunction "VLOGIC_8") (pintype "bidirectional"))
      (node (ref "U902") (pin "1") (pinfunction "VDDIO_1") (pintype "power_in"))
      (node (ref "U902") (pin "6") (pinfunction "VS_6") (pintype "power_in"))
      (node (ref "U902") (pin "7") (pinfunction "CS_7") (pintype "input"))
    )
    (net (code "56") (name "unconnected-(J701-CD-PadCD1)") (class "Default")
      (node (ref "J701") (pin "CD1") (pinfunction "CD_CD1") (pintype "bidirectional"))
    )
    (net (code "57") (name "unconnected-(J701-NC-Pad1)") (class "Default")
      (node (ref "J701") (pin "1") (pinfunction "NC_1") (pintype "bidirectional"))
    )
    (net (code "58") (name "unconnected-(J701-RSV-Pad8)") (class "Default")
      (node (ref "J701") (pin "8") (pinfunction "RSV_8") (pintype "bidirectional"))
    )
    (net (code "59") (name "unconnected-(U003-(AD0.1{slash}CAP0.2{slash}MAT0.2)P0.28-Pad13)") (class "Default")
      (node (ref "U003") (pin "13") (pinfunction "(AD0.1/CAP0.2/MAT0.2)P0.28_13") (pintype "bidirectional"))
    )
    (net (code "60") (name "unconnected-(U003-(AD0.2{slash}CAP0.3{slash}MAT0.3)P0.29-Pad14)") (class "Default")
      (node (ref "U003") (pin "14") (pinfunction "(AD0.2/CAP0.3/MAT0.3)P0.29_14") (pintype "bidirectional"))
    )
    (net (code "61") (name "unconnected-(U003-(AD0.4{slash}AOUT)P0.25-Pad9)") (class "Default")
      (node (ref "U003") (pin "9") (pinfunction "(AD0.4/AOUT)P0.25_9") (pintype "bidirectional"))
    )
    (net (code "62") (name "unconnected-(U003-(AD1.7{slash}CAP0.0{slash}MAT0.0)P0.22-Pad2)") (class "Default")
      (node (ref "U003") (pin "2") (pinfunction "(AD1.7/CAP0.0/MAT0.0)P0.22_2") (pintype "bidirectional"))
    )
    (net (code "63") (name "unconnected-(U003-(CAP1.3{slash}MISO1{slash}MAT1.3)P0.18-Pad53)") (class "Default")
      (node (ref "U003") (pin "53") (pinfunction "(CAP1.3/MISO1/MAT1.3)P0.18_53") (pintype "bidirectional"))
    )
    (net (code "64") (name "unconnected-(U003-(CTS1{slash}CAP1.1{slash}SCL1)P0.11-Pad37)") (class "Default")
      (node (ref "U003") (pin "37") (pinfunction "(CTS1/CAP1.1/SCL1)P0.11_37") (pintype "bidirectional"))
    )
    (net (code "65") (name "unconnected-(U003-(DSR1{slash}MAT1.0{slash}AD1.3)P0.12-Pad38)") (class "Default")
      (node (ref "U003") (pin "38") (pinfunction "(DSR1/MAT1.0/AD1.3)P0.12_38") (pintype "bidirectional"))
    )
    (net (code "66") (name "unconnected-(U003-(DTR1{slash}MAT1.1{slash}AD1.4)P0.13-Pad39)") (class "Default")
      (node (ref "U003") (pin "39") (pinfunction "(DTR1/MAT1.1/AD1.4)P0.13_39") (pintype "bidirectional"))
    )
    (net (code "67") (name "unconnected-(U003-(EINT0{slash}MAT0.2{slash}CAP0.2)P0.16-Pad46)") (class "Default")
      (node (ref "U003") (pin "46") (pinfunction "(EINT0/MAT0.2/CAP0.2)P0.16_46") (pintype "bidirectional"))
    )
    (net (code "68") (name "unconnected-(U003-(MAT1.2{slash}MOSI1{slash}CAP1.2)P0.19-Pad54)") (class "Default")
      (node (ref "U003") (pin "54") (pinfunction "(MAT1.2/MOSI1/CAP1.2)P0.19_54") (pintype "bidirectional"))
    )
    (net (code "69") (name "unconnected-(U003-(MAT1.3{slash}SSEL1{slash}EINT3)P0.20-Pad55)") (class "Default")
      (node (ref "U003") (pin "55") (pinfunction "(MAT1.3/SSEL1/EINT3)P0.20_55") (pintype "bidirectional"))
    )
    (net (code "70") (name "unconnected-(U003-(PWM5{slash}AD1.6{slash}CAP1.3)P0.21-Pad1)") (class "Default")
      (node (ref "U003") (pin "1") (pinfunction "(PWM5/AD1.6/CAP1.3)P0.21_1") (pintype "bidirectional"))
    )
    (net (code "71") (name "unconnected-(U003-P1.16(TRACEPKT0)-Pad16)") (class "Default")
      (node (ref "U003") (pin "16") (pinfunction "P1.16(TRACEPKT0)_16") (pintype "bidirectional"))
    )
    (net (code "72") (name "unconnected-(U003-P1.17(TRACEPKT1)-Pad12)") (class "Default")
      (node (ref "U003") (pin "12") (pinfunction "P1.17(TRACEPKT1)_12") (pintype "bidirectional"))
    )
    (net (code "73") (name "unconnected-(U003-P1.18(TRACEPKT2)-Pad8)") (class "Default")
      (node (ref "U003") (pin "8") (pinfunction "P1.18(TRACEPKT2)_8") (pintype "bidirectional"))
    )
    (net (code "74") (name "unconnected-(U003-P1.19(TRACEPKT3)-Pad4)") (class "Default")
      (node (ref "U003") (pin "4") (pinfunction "P1.19(TRACEPKT3)_4") (pintype "bidirectional"))
    )
    (net (code "75") (name "unconnected-(U003-P1.20(TRACESYNC)-Pad48)") (class "Default")
      (node (ref "U003") (pin "48") (pinfunction "P1.20(TRACESYNC)_48") (pintype "bidirectional"))
    )
    (net (code "76") (name "unconnected-(U003-P1.21(PIPESTAT0)-Pad44)") (class "Default")
      (node (ref "U003") (pin "44") (pinfunction "P1.21(PIPESTAT0)_44") (pintype "bidirectional"))
    )
    (net (code "77") (name "unconnected-(U003-P1.22(PIPESTAT1)-Pad40)") (class "Default")
      (node (ref "U003") (pin "40") (pinfunction "P1.22(PIPESTAT1)_40") (pintype "bidirectional"))
    )
    (net (code "78") (name "unconnected-(U003-P1.23(PIPESTAT2)-Pad36)") (class "Default")
      (node (ref "U003") (pin "36") (pinfunction "P1.23(PIPESTAT2)_36") (pintype "bidirectional"))
    )
    (net (code "79") (name "unconnected-(U003-P1.24(TRACECLK)-Pad32)") (class "Default")
      (node (ref "U003") (pin "32") (pinfunction "P1.24(TRACECLK)_32") (pintype "bidirectional"))
    )
    (net (code "80") (name "unconnected-(U003-P1.25(EXTIN0)-Pad28)") (class "Default")
      (node (ref "U003") (pin "28") (pinfunction "P1.25(EXTIN0)_28") (pintype "bidirectional"))
    )
    (net (code "81") (name "unconnected-(U003-P1.26(RTCK)-Pad24)") (class "Default")
      (node (ref "U003") (pin "24") (pinfunction "P1.26(RTCK)_24") (pintype "bidirectional"))
    )
    (net (code "82") (name "unconnected-(U003-P1.27(TDO)-Pad64)") (class "Default")
      (node (ref "U003") (pin "64") (pinfunction "P1.27(TDO)_64") (pintype "bidirectional"))
    )
    (net (code "83") (name "unconnected-(U003-P1.28(TDI)-Pad60)") (class "Default")
      (node (ref "U003") (pin "60") (pinfunction "P1.28(TDI)_60") (pintype "bidirectional"))
    )
    (net (code "84") (name "unconnected-(U003-P1.29(TCK)-Pad56)") (class "Default")
      (node (ref "U003") (pin "56") (pinfunction "P1.29(TCK)_56") (pintype "bidirectional"))
    )
    (net (code "85") (name "unconnected-(U003-P1.30(TMS)-Pad52)") (class "Default")
      (node (ref "U003") (pin "52") (pinfunction "P1.30(TMS)_52") (pintype "bidirectional"))
    )
    (net (code "86") (name "unconnected-(U003-P1.31({slash}TRST)-Pad20)") (class "Default")
      (node (ref "U003") (pin "20") (pinfunction "P1.31(/TRST)_20") (pintype "bidirectional"))
    )
    (net (code "87") (name "unconnected-(U003-RTXC2-Pad5)") (class "Default")
      (node (ref "U003") (pin "5") (pinfunction "RTXC2_5") (pintype "output"))
    )
    (net (code "88") (name "unconnected-(U601-CLKOUT-Pad22)") (class "Default")
      (node (ref "U601") (pin "22") (pinfunction "CLKOUT_22") (pintype "bidirectional"))
    )
    (net (code "89") (name "unconnected-(U601-ES_CL-Pad7)") (class "Default")
      (node (ref "U601") (pin "7") (pinfunction "ES_CL_7") (pintype "bidirectional"))
    )
    (net (code "90") (name "unconnected-(U601-ES_DA-Pad6)") (class "Default")
      (node (ref "U601") (pin "6") (pinfunction "ES_DA_6") (pintype "bidirectional"))
    )
    (net (code "91") (name "unconnected-(U902-INT1-Pad8)") (class "Default")
      (node (ref "U902") (pin "8") (pinfunction "INT1_8") (pintype "output"))
    )
    (net (code "92") (name "unconnected-(U902-INT2-Pad9)") (class "Default")
      (node (ref "U902") (pin "9") (pinfunction "INT2_9") (pintype "output"))
    )
  )
)
